# indsensor3.net
KiCad netlist of a schematic drawn in EAGLE
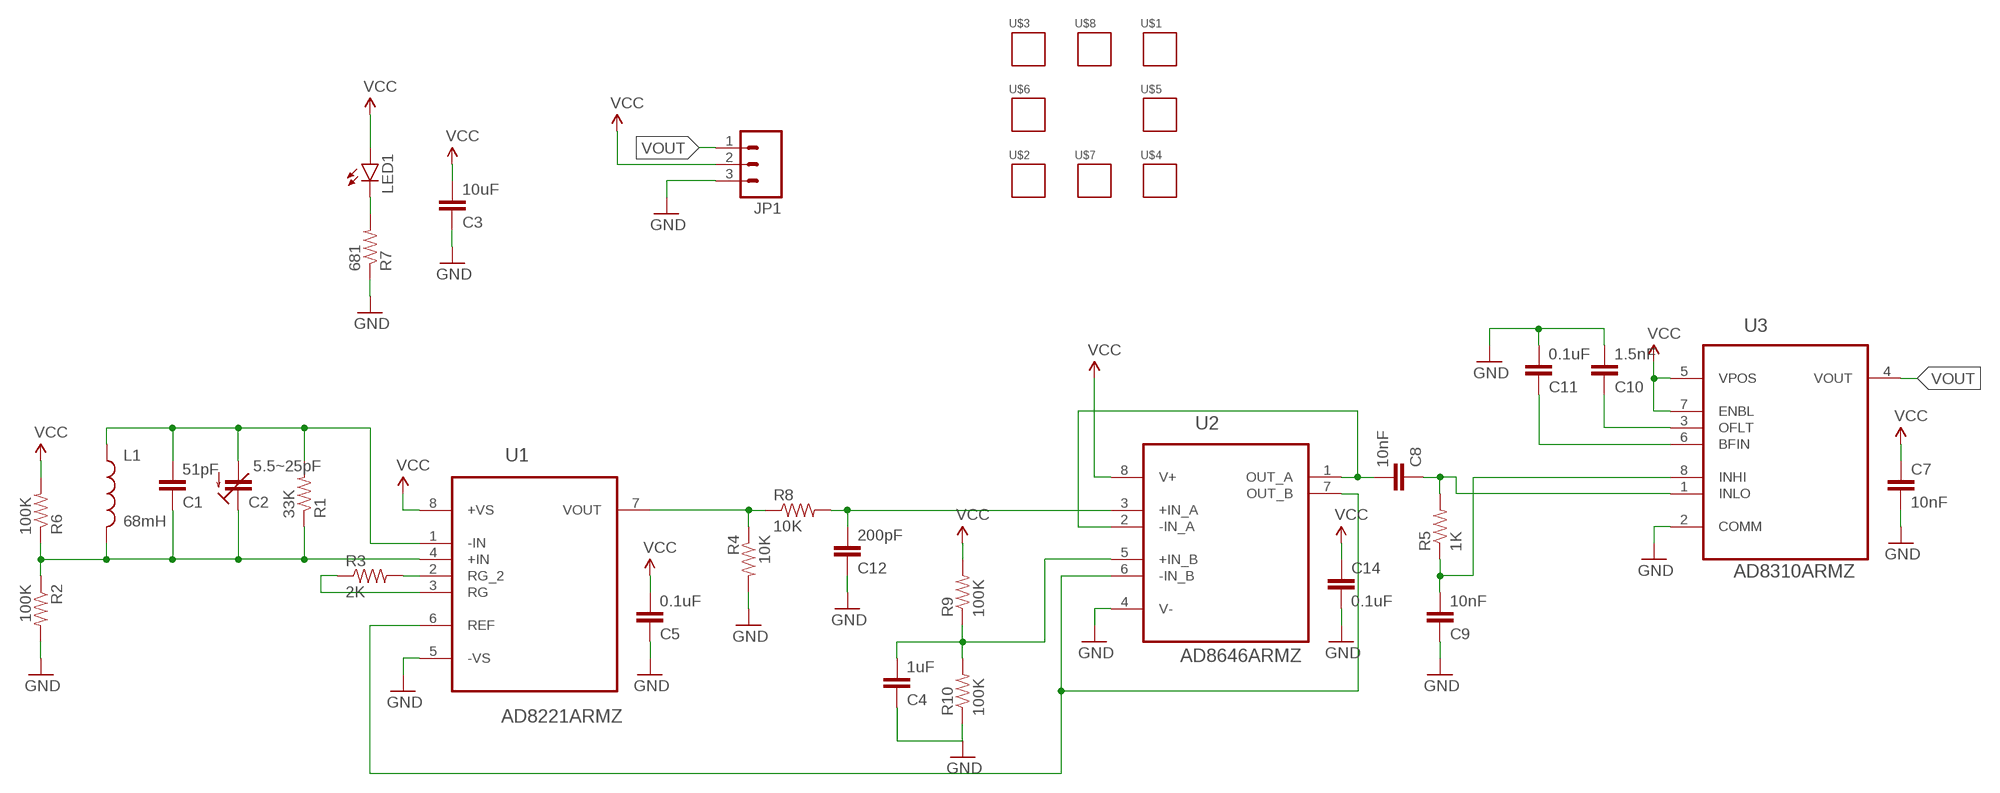
[diagram p0: schematic, sheet 1]

(export (version "E")
  (design (tool "Eeschema 10.0.6"))
  (components
    (comp (ref "C1")
      (value "51pF")
      (footprint "eagle-import:0603-CAP")
      (libsource (lib "eagle-import") (part "CAP0603-CAP"))
    )
    (comp (ref "C2")
      (value "5.5~25pF")
      (footprint "eagle-import:TRIMCAP-TZY")
      (libsource (lib "eagle-import") (part "TRIMCAP-TZY"))
    )
    (comp (ref "C3")
      (value "10uF")
      (footprint "eagle-import:1206")
      (libsource (lib "eagle-import") (part "SparkFun-Passives_CAP1206"))
    )
    (comp (ref "C4")
      (value "1uF")
      (footprint "eagle-import:0603-CAP")
      (libsource (lib "eagle-import") (part "CAP0603-CAP"))
    )
    (comp (ref "C5")
      (value "0.1uF")
      (footprint "eagle-import:0603-CAP")
      (libsource (lib "eagle-import") (part "CAP0603-CAP"))
    )
    (comp (ref "C7")
      (value "10nF")
      (footprint "eagle-import:0603-CAP")
      (libsource (lib "eagle-import") (part "CAP0603-CAP"))
    )
    (comp (ref "C8")
      (value "10nF")
      (footprint "eagle-import:0603-CAP")
      (libsource (lib "eagle-import") (part "CAP0603-CAP"))
    )
    (comp (ref "C9")
      (value "10nF")
      (footprint "eagle-import:0603-CAP")
      (libsource (lib "eagle-import") (part "CAP0603-CAP"))
    )
    (comp (ref "C10")
      (value "1.5nF")
      (footprint "eagle-import:0603-CAP")
      (libsource (lib "eagle-import") (part "CAP0603-CAP"))
    )
    (comp (ref "C11")
      (value "0.1uF")
      (footprint "eagle-import:0603-CAP")
      (libsource (lib "eagle-import") (part "CAP0603-CAP"))
    )
    (comp (ref "C12")
      (value "200pF")
      (footprint "eagle-import:0603-CAP")
      (libsource (lib "eagle-import") (part "CAP0603-CAP"))
    )
    (comp (ref "C14")
      (value "0.1uF")
      (footprint "eagle-import:0603-CAP")
      (libsource (lib "eagle-import") (part "CAP0603-CAP"))
    )
    (comp (ref "JP1")
      (value "M03LOCK")
      (footprint "eagle-import:1X03_LOCK")
      (libsource (lib "eagle-import") (part "M03LOCK"))
    )
    (comp (ref "L1")
      (value "68mH")
      (footprint "eagle-import:RLB0912")
      (libsource (lib "eagle-import") (part "INDUCTORRLB0912"))
    )
    (comp (ref "LED1")
      (value "LED0603")
      (footprint "eagle-import:LED-0603")
      (libsource (lib "eagle-import") (part "LED0603"))
    )
    (comp (ref "R1")
      (value "33K")
      (footprint "eagle-import:0603-RES")
      (libsource (lib "eagle-import") (part "RESISTOR0603"))
    )
    (comp (ref "R2")
      (value "100K")
      (footprint "eagle-import:0603-RES")
      (libsource (lib "eagle-import") (part "RESISTOR0603"))
    )
    (comp (ref "R3")
      (value "2K")
      (footprint "eagle-import:0603-RES")
      (libsource (lib "eagle-import") (part "RESISTOR0603"))
    )
    (comp (ref "R4")
      (value "10K")
      (footprint "eagle-import:0603-RES")
      (libsource (lib "eagle-import") (part "RESISTOR0603"))
    )
    (comp (ref "R5")
      (value "1K")
      (footprint "eagle-import:0603-RES")
      (libsource (lib "eagle-import") (part "RESISTOR0603"))
    )
    (comp (ref "R6")
      (value "100K")
      (footprint "eagle-import:0603-RES")
      (libsource (lib "eagle-import") (part "RESISTOR0603"))
    )
    (comp (ref "R7")
      (value "681")
      (footprint "eagle-import:0603-RES")
      (libsource (lib "eagle-import") (part "RESISTOR0603"))
    )
    (comp (ref "R8")
      (value "10K")
      (footprint "eagle-import:0603-RES")
      (libsource (lib "eagle-import") (part "RESISTOR0603"))
    )
    (comp (ref "R9")
      (value "100K")
      (footprint "eagle-import:0603-RES")
      (libsource (lib "eagle-import") (part "RESISTOR0603"))
    )
    (comp (ref "R10")
      (value "100K")
      (footprint "eagle-import:0603-RES")
      (libsource (lib "eagle-import") (part "RESISTOR0603"))
    )
    (comp (ref "U$1")
      (value "SHIELD-CORNER")
      (footprint "eagle-import:SHIELD-CORNER")
      (libsource (lib "eagle-import") (part "SHIELD-CORNER"))
    )
    (comp (ref "U$2")
      (value "SHIELD-CORNER")
      (footprint "eagle-import:SHIELD-CORNER")
      (libsource (lib "eagle-import") (part "SHIELD-CORNER"))
    )
    (comp (ref "U$3")
      (value "SHIELD-CORNER")
      (footprint "eagle-import:SHIELD-CORNER")
      (libsource (lib "eagle-import") (part "SHIELD-CORNER"))
    )
    (comp (ref "U$4")
      (value "SHIELD-CORNER")
      (footprint "eagle-import:SHIELD-CORNER")
      (libsource (lib "eagle-import") (part "SHIELD-CORNER"))
    )
    (comp (ref "U$5")
      (value "SHIELD-MIDDLE")
      (footprint "eagle-import:SHIELD-MIDDLE")
      (libsource (lib "eagle-import") (part "SHIELD-MIDDLE"))
    )
    (comp (ref "U$6")
      (value "SHIELD-MIDDLE")
      (footprint "eagle-import:SHIELD-MIDDLE")
      (libsource (lib "eagle-import") (part "SHIELD-MIDDLE"))
    )
    (comp (ref "U$7")
      (value "SHIELD-MIDDLEPART")
      (footprint "eagle-import:SHIELD-MIDDLEPART")
      (libsource (lib "eagle-import") (part "SHIELD-MIDDLEPART"))
    )
    (comp (ref "U$8")
      (value "SHIELD-MIDDLE3")
      (footprint "eagle-import:SHIELD-MIDDLE3")
      (libsource (lib "eagle-import") (part "SHIELD-MIDDLE3"))
    )
    (comp (ref "U1")
      (value "AD8221ARMZ")
      (footprint "eagle-import:SOP65P490X110-8N")
      (libsource (lib "eagle-import") (part "AD8221ARMZ"))
    )
    (comp (ref "U2")
      (value "AD8646ARMZ")
      (footprint "eagle-import:SOP65P490X110-8N")
      (libsource (lib "eagle-import") (part "AD8646ARMZ"))
    )
    (comp (ref "U3")
      (value "AD8310ARMZ")
      (footprint "eagle-import:SOP65P490X110-8N")
      (libsource (lib "eagle-import") (part "AD8310ARMZ"))
    )
  )
  (nets
    (net (code "1") (name "GND") (class "Default")
      (node (ref "C10") (pin "2") (pinfunction "2_2") (pintype "passive"))
      (node (ref "C11") (pin "2") (pinfunction "2_2") (pintype "passive"))
      (node (ref "C12") (pin "1") (pinfunction "1_1") (pintype "passive"))
      (node (ref "C14") (pin "2") (pinfunction "2_2") (pintype "passive"))
      (node (ref "C3") (pin "1") (pinfunction "1_1") (pintype "passive"))
      (node (ref "C4") (pin "1") (pinfunction "1_1") (pintype "passive"))
      (node (ref "C5") (pin "1") (pinfunction "1_1") (pintype "passive"))
      (node (ref "C7") (pin "2") (pinfunction "2_2") (pintype "passive"))
      (node (ref "C9") (pin "1") (pinfunction "1_1") (pintype "passive"))
      (node (ref "JP1") (pin "3") (pinfunction "3_3") (pintype "passive"))
      (node (ref "R10") (pin "1") (pinfunction "1_1") (pintype "passive"))
      (node (ref "R2") (pin "2") (pinfunction "2_2") (pintype "passive"))
      (node (ref "R4") (pin "2") (pinfunction "2_2") (pintype "passive"))
      (node (ref "R7") (pin "1") (pinfunction "1_1") (pintype "passive"))
      (node (ref "U1") (pin "5") (pinfunction "-VS_5") (pintype "power_in"))
      (node (ref "U2") (pin "4") (pinfunction "V-_4") (pintype "power_in"))
      (node (ref "U3") (pin "2") (pinfunction "COMM_2") (pintype "passive"))
    )
    (net (code "2") (name "Net-(C2-A)") (class "Default")
      (node (ref "C1") (pin "2") (pinfunction "2_2") (pintype "passive"))
      (node (ref "C2") (pin "1") (pinfunction "A_1") (pintype "passive"))
      (node (ref "L1") (pin "1") (pinfunction "1_1") (pintype "passive"))
      (node (ref "R1") (pin "2") (pinfunction "2_2") (pintype "passive"))
      (node (ref "U1") (pin "1") (pinfunction "-IN_1") (pintype "input"))
    )
    (net (code "3") (name "Net-(C2-E)") (class "Default")
      (node (ref "C1") (pin "1") (pinfunction "1_1") (pintype "passive"))
      (node (ref "C2") (pin "2") (pinfunction "E_2") (pintype "passive"))
      (node (ref "L1") (pin "2") (pinfunction "2_2") (pintype "passive"))
      (node (ref "R1") (pin "1") (pinfunction "1_1") (pintype "passive"))
      (node (ref "R2") (pin "1") (pinfunction "1_1") (pintype "passive"))
      (node (ref "R6") (pin "1") (pinfunction "1_1") (pintype "passive"))
      (node (ref "U1") (pin "4") (pinfunction "+IN_4") (pintype "input"))
    )
    (net (code "4") (name "Net-(LED1-PadC)") (class "Default")
      (node (ref "LED1") (pin "C") (pinfunction "C_C") (pintype "passive"))
      (node (ref "R7") (pin "2") (pinfunction "2_2") (pintype "passive"))
    )
    (net (code "5") (name "Net-(U1-REF)") (class "Default")
      (node (ref "U1") (pin "6") (pinfunction "REF_6") (pintype "passive"))
      (node (ref "U2") (pin "6") (pinfunction "-IN_B_6") (pintype "input"))
      (node (ref "U2") (pin "7") (pinfunction "OUT_B_7") (pintype "output"))
    )
    (net (code "6") (name "Net-(U1-RG)") (class "Default")
      (node (ref "R3") (pin "1") (pinfunction "1_1") (pintype "passive"))
      (node (ref "U1") (pin "3") (pinfunction "RG_3") (pintype "input"))
    )
    (net (code "7") (name "Net-(U1-RG_2)") (class "Default")
      (node (ref "R3") (pin "2") (pinfunction "2_2") (pintype "passive"))
      (node (ref "U1") (pin "2") (pinfunction "RG_2_2") (pintype "input"))
    )
    (net (code "8") (name "Net-(U1-VOUT)") (class "Default")
      (node (ref "R4") (pin "1") (pinfunction "1_1") (pintype "passive"))
      (node (ref "R8") (pin "1") (pinfunction "1_1") (pintype "passive"))
      (node (ref "U1") (pin "7") (pinfunction "VOUT_7") (pintype "output"))
    )
    (net (code "9") (name "Net-(U2-+IN_A)") (class "Default")
      (node (ref "C12") (pin "2") (pinfunction "2_2") (pintype "passive"))
      (node (ref "R8") (pin "2") (pinfunction "2_2") (pintype "passive"))
      (node (ref "U2") (pin "3") (pinfunction "+IN_A_3") (pintype "input"))
    )
    (net (code "10") (name "Net-(U2-+IN_B)") (class "Default")
      (node (ref "C4") (pin "2") (pinfunction "2_2") (pintype "passive"))
      (node (ref "R10") (pin "2") (pinfunction "2_2") (pintype "passive"))
      (node (ref "R9") (pin "1") (pinfunction "1_1") (pintype "passive"))
      (node (ref "U2") (pin "5") (pinfunction "+IN_B_5") (pintype "input"))
    )
    (net (code "11") (name "Net-(U2--IN_A)") (class "Default")
      (node (ref "C8") (pin "2") (pinfunction "2_2") (pintype "passive"))
      (node (ref "U2") (pin "1") (pinfunction "OUT_A_1") (pintype "output"))
      (node (ref "U2") (pin "2") (pinfunction "-IN_A_2") (pintype "input"))
    )
    (net (code "12") (name "Net-(U3-BFIN)") (class "Default")
      (node (ref "C11") (pin "1") (pinfunction "1_1") (pintype "passive"))
      (node (ref "U3") (pin "6") (pinfunction "BFIN_6") (pintype "input"))
    )
    (net (code "13") (name "Net-(U3-INHI)") (class "Default")
      (node (ref "C9") (pin "2") (pinfunction "2_2") (pintype "passive"))
      (node (ref "R5") (pin "1") (pinfunction "1_1") (pintype "passive"))
      (node (ref "U3") (pin "8") (pinfunction "INHI_8") (pintype "input"))
    )
    (net (code "14") (name "Net-(U3-INLO)") (class "Default")
      (node (ref "C8") (pin "1") (pinfunction "1_1") (pintype "passive"))
      (node (ref "R5") (pin "2") (pinfunction "2_2") (pintype "passive"))
      (node (ref "U3") (pin "1") (pinfunction "INLO_1") (pintype "input"))
    )
    (net (code "15") (name "Net-(U3-OFLT)") (class "Default")
      (node (ref "C10") (pin "1") (pinfunction "1_1") (pintype "passive"))
      (node (ref "U3") (pin "3") (pinfunction "OFLT_3") (pintype "passive"))
    )
    (net (code "16") (name "VCC") (class "Default")
      (node (ref "C14") (pin "1") (pinfunction "1_1") (pintype "passive"))
      (node (ref "C3") (pin "2") (pinfunction "2_2") (pintype "passive"))
      (node (ref "C5") (pin "2") (pinfunction "2_2") (pintype "passive"))
      (node (ref "C7") (pin "1") (pinfunction "1_1") (pintype "passive"))
      (node (ref "JP1") (pin "2") (pinfunction "2_2") (pintype "passive"))
      (node (ref "LED1") (pin "A") (pinfunction "A_A") (pintype "passive"))
      (node (ref "R6") (pin "2") (pinfunction "2_2") (pintype "passive"))
      (node (ref "R9") (pin "2") (pinfunction "2_2") (pintype "passive"))
      (node (ref "U1") (pin "8") (pinfunction "+VS_8") (pintype "power_in"))
      (node (ref "U2") (pin "8") (pinfunction "V+_8") (pintype "power_in"))
      (node (ref "U3") (pin "5") (pinfunction "VPOS_5") (pintype "power_in"))
      (node (ref "U3") (pin "7") (pinfunction "ENBL_7") (pintype "input"))
    )
    (net (code "17") (name "VOUT") (class "Default")
      (node (ref "JP1") (pin "1") (pinfunction "1_1") (pintype "passive"))
      (node (ref "U3") (pin "4") (pinfunction "VOUT_4") (pintype "output"))
    )
  )
)
